# mainboard_V3_2.net
KiCad netlist of a schematic drawn in EasyEDA Pro
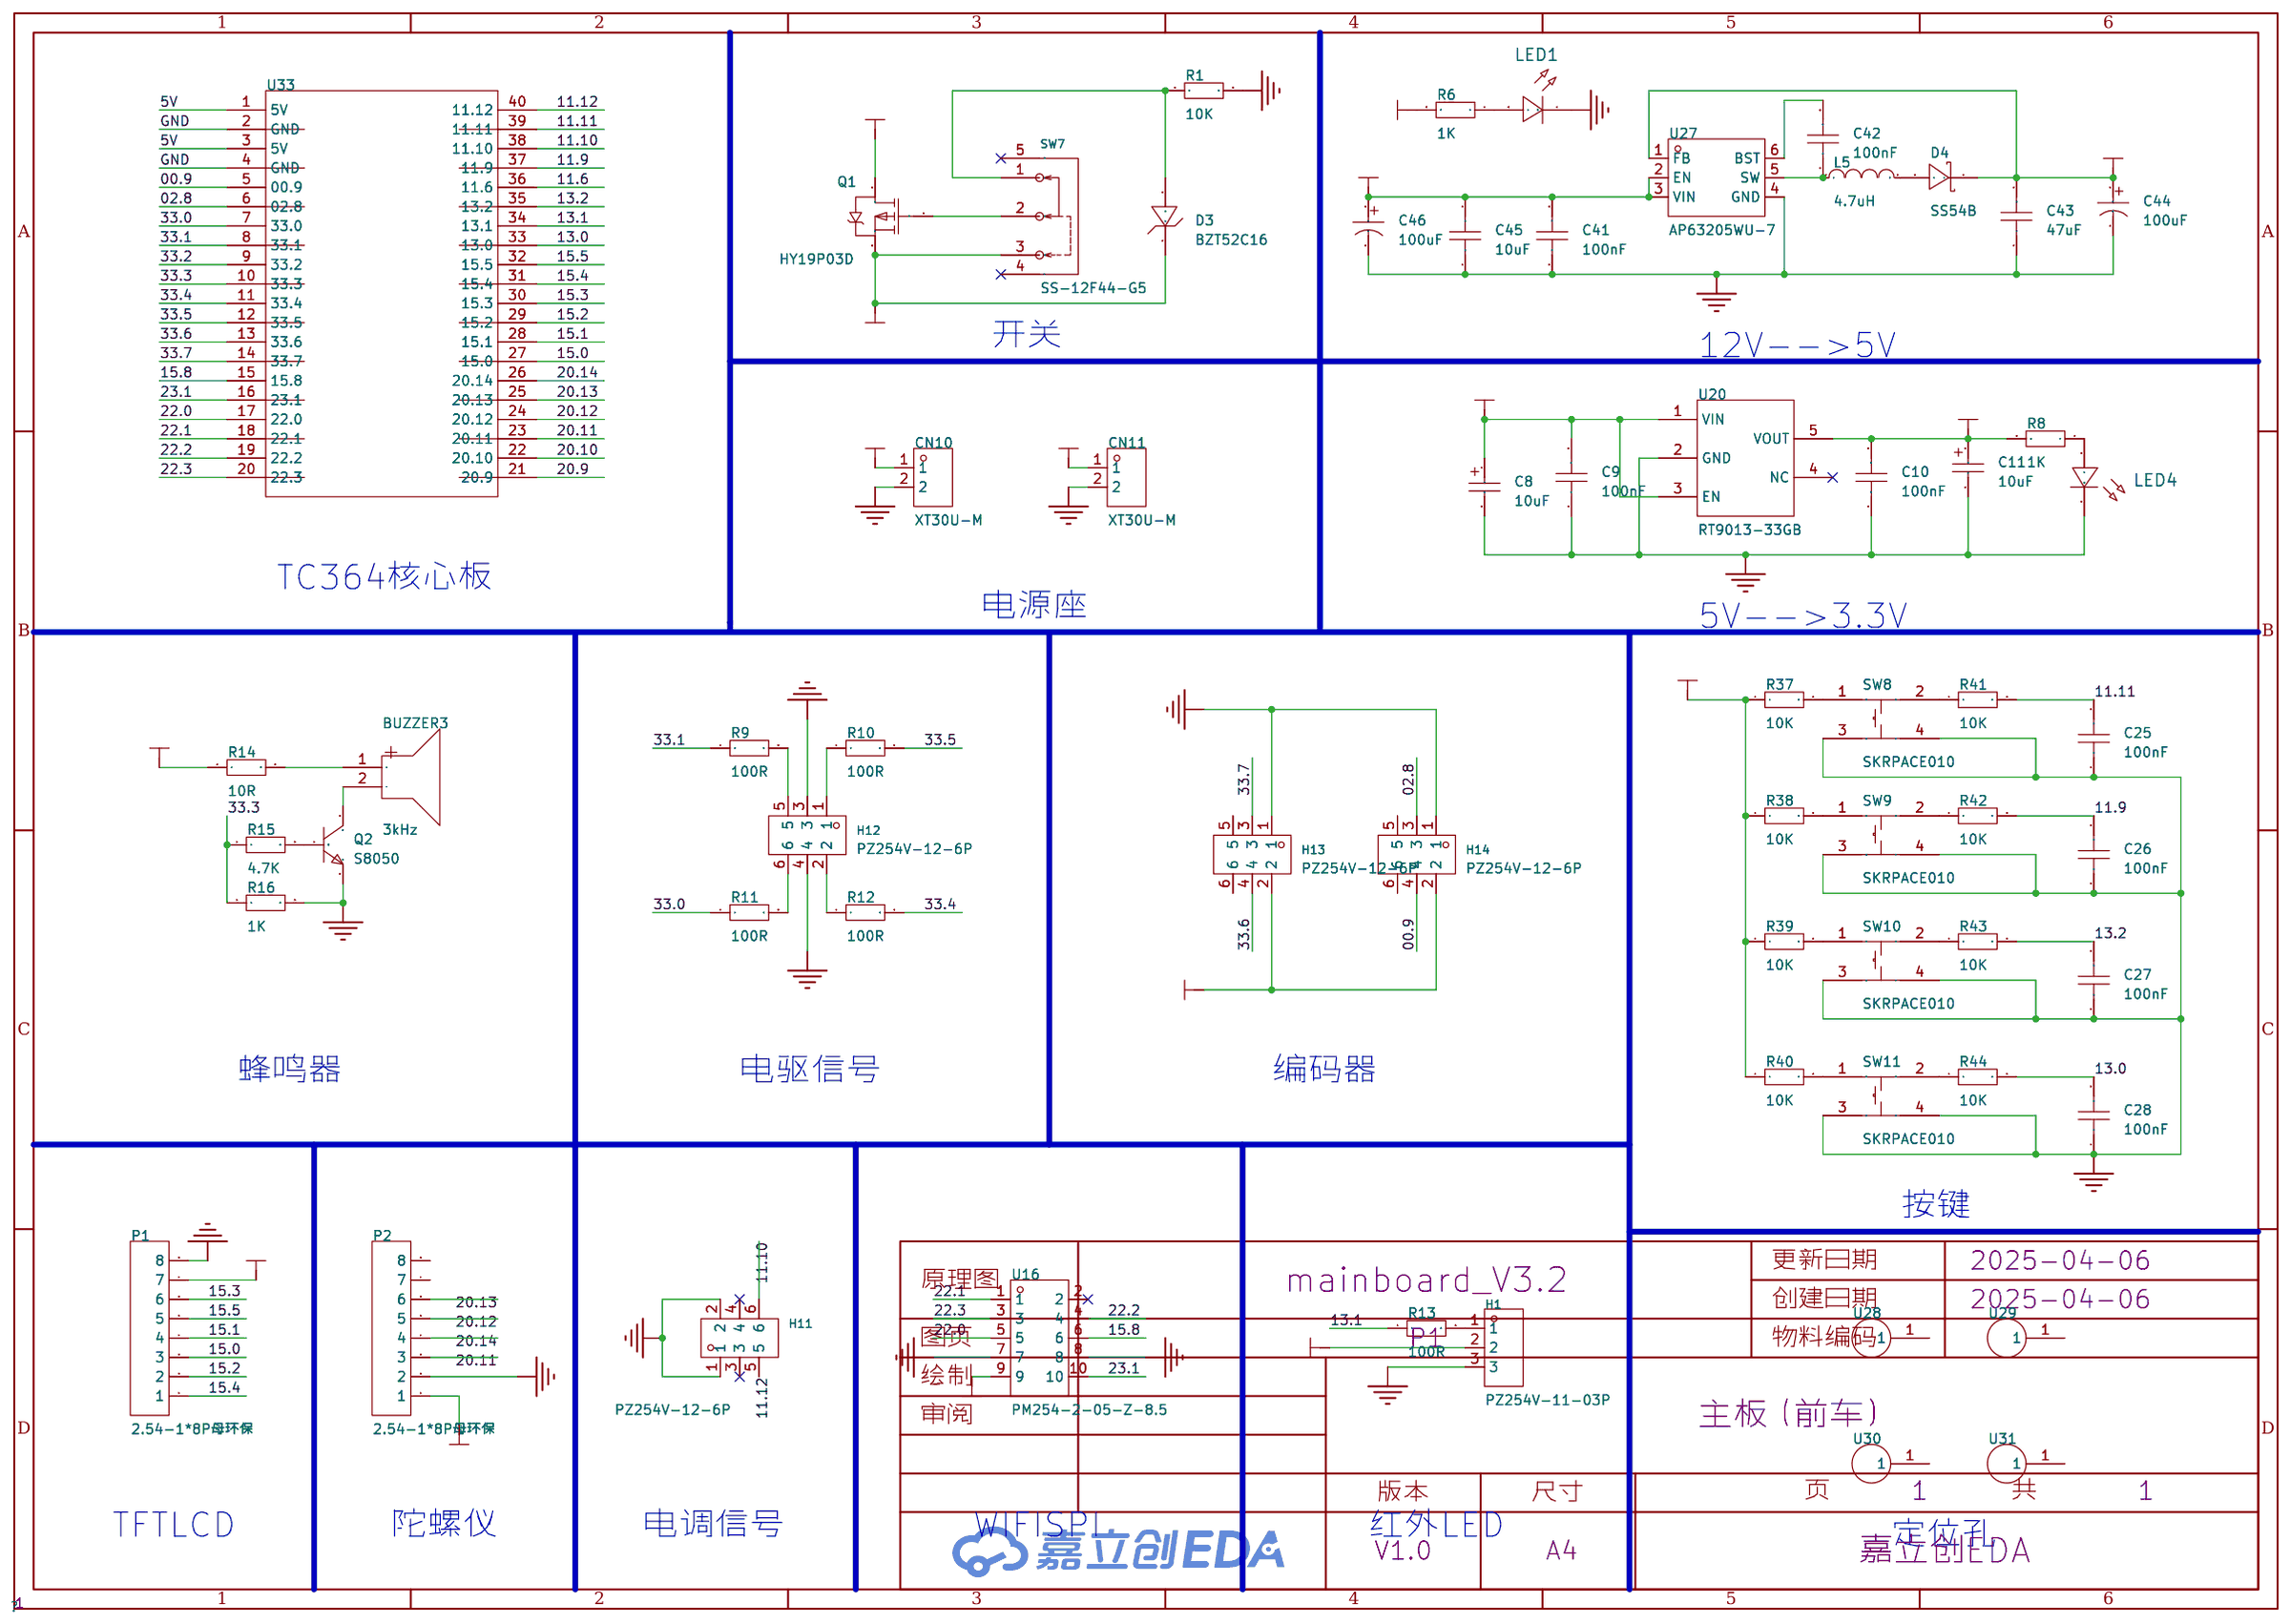
[diagram p0: schematic sheet]

(export (version "E")
  (design (tool "Eeschema 10.0.6"))
  (components
    (comp (ref "BUZZER3")
      (value "3kHz")
      (footprint "easyedapro:BUZ-TH_BD9.0-P5.00-D0.6-FD")
      (description "驱动方式:有源(内含驱动线路);构造类型:电磁式;频率:3kHz;声压(SPL):85dB@10cm;")
      (fields (field (name "Manufacturer Part") "HNB09A03") (field (name "Manufacturer") "华能"))
      (libsource (lib "easyedapro") (part "HNB09A03"))
    )
    (comp (ref "C8")
      (value "10uF")
      (footprint "easyedapro:CAP-SMD_L3.2-W1.6-RD-C7171")
      (description "容值:10uF;精度:±10%;额定电压:16V;等效串联电阻:3Ω@100kHz;")
      (fields (field (name "Manufacturer Part") "TAJA106K016RNJ") (field (name "Manufacturer") "Kyocera AVX"))
      (libsource (lib "easyedapro") (part "TAJA106K016RNJ"))
    )
    (comp (ref "C9")
      (value "100nF")
      (footprint "easyedapro:C0603")
      (description "容值:100nF;精度:±10%;额定电压:50V;材质(温度系数):X7R;")
      (fields
        (field (name "Manufacturer Part") "CC0603KRX7R9BB104")
        (field (name "Manufacturer") "YAGEO(国巨)")
      )
      (libsource (lib "easyedapro") (part "CC0603KRX7R9BB104"))
    )
    (comp (ref "C10")
      (value "100nF")
      (footprint "easyedapro:C0603")
      (description "容值:100nF;精度:±10%;额定电压:50V;材质(温度系数):X7R;")
      (fields
        (field (name "Manufacturer Part") "CC0603KRX7R9BB104")
        (field (name "Manufacturer") "YAGEO(国巨)")
      )
      (libsource (lib "easyedapro") (part "CC0603KRX7R9BB104"))
    )
    (comp (ref "C11")
      (value "10uF")
      (footprint "easyedapro:CAP-SMD_L3.2-W1.6-RD-C7171")
      (description "容值:10uF;精度:±10%;额定电压:16V;等效串联电阻:3Ω@100kHz;")
      (fields (field (name "Manufacturer Part") "TAJA106K016RNJ") (field (name "Manufacturer") "Kyocera AVX"))
      (libsource (lib "easyedapro") (part "TAJA106K016RNJ"))
    )
    (comp (ref "C25")
      (value "100nF")
      (footprint "easyedapro:C0603")
      (libsource (lib "easyedapro") (part "CapAcitance"))
    )
    (comp (ref "C26")
      (value "100nF")
      (footprint "easyedapro:C0603")
      (libsource (lib "easyedapro") (part "CapAcitance"))
    )
    (comp (ref "C27")
      (value "100nF")
      (footprint "easyedapro:C0603")
      (libsource (lib "easyedapro") (part "CapAcitance"))
    )
    (comp (ref "C28")
      (value "100nF")
      (footprint "easyedapro:C0603")
      (libsource (lib "easyedapro") (part "CapAcitance"))
    )
    (comp (ref "C41")
      (value "100nF")
      (footprint "easyedapro:C0603")
      (libsource (lib "easyedapro") (part "CapAcitance"))
    )
    (comp (ref "C42")
      (value "100nF")
      (footprint "easyedapro:C0603")
      (libsource (lib "easyedapro") (part "CapAcitance"))
    )
    (comp (ref "C43")
      (value "47uF")
      (footprint "easyedapro:C0805")
      (description "容值:47uF;精度:±20%;额定电压:10V;材质(温度系数):X5R;")
      (fields
        (field (name "Manufacturer Part") "CGA0805X5R476M100MT")
        (field (name "Manufacturer") "HRE(芯声)")
      )
      (libsource (lib "easyedapro") (part "CGA0805X5R476M100MT"))
    )
    (comp (ref "C44")
      (value "100uF")
      (footprint "easyedapro:CAP-TH_BD6.3-P2.50-D1.0-FD")
      (description "容值:100uF;精度:±20%;额定电压:35V;纹波电流:2.35A@100kHz;等效串联电阻:50mΩ@100kHz;类型:-;")
      (fields
        (field (name "Manufacturer Part") "SPZ1VM101E08O00RAXXX")
        (field (name "Manufacturer") "AISHI(艾华集团)")
      )
      (libsource (lib "easyedapro") (part "SPZ1VM101E08000R"))
    )
    (comp (ref "C45")
      (value "10uF")
      (footprint "easyedapro:C0603")
      (libsource (lib "easyedapro") (part "CapAcitance"))
    )
    (comp (ref "C46")
      (value "100uF")
      (footprint "easyedapro:CAP-TH_BD6.3-P2.50-D1.0-FD")
      (description "容值:100uF;精度:±20%;额定电压:35V;纹波电流:2.35A@100kHz;等效串联电阻:50mΩ@100kHz;类型:-;")
      (fields
        (field (name "Manufacturer Part") "SPZ1VM101E08O00RAXXX")
        (field (name "Manufacturer") "AISHI(艾华集团)")
      )
      (libsource (lib "easyedapro") (part "SPZ1VM101E08000R"))
    )
    (comp (ref "CN10")
      (value "XT30U-M")
      (footprint "easyedapro:CONN-TH_XT30U-M")
      (description "类别:-;类型1:-;")
      (fields (field (name "Manufacturer") "AMASS(艾迈斯)"))
      (libsource (lib "easyedapro") (part "XT30U-M"))
    )
    (comp (ref "CN11")
      (value "XT30U-M")
      (footprint "easyedapro:CONN-TH_XT30U-M")
      (description "类别:-;类型1:-;")
      (fields (field (name "Manufacturer") "AMASS(艾迈斯)"))
      (libsource (lib "easyedapro") (part "XT30U-M"))
    )
    (comp (ref "D3")
      (value "BZT52C16")
      (footprint "easyedapro:SOD-123_L2.7-W1.6-LS3.7-RD")
      (description "二极管配置:独立式;稳压值(标称值):16V;稳压值(范围):15.3V~17.1V;功率:500mW;精度:-;")
      (fields (field (name "Manufacturer") "BORN(伯恩半导体)"))
      (libsource (lib "easyedapro") (part "BZT52C16_C266570"))
    )
    (comp (ref "D4")
      (value "SS54B")
      (footprint "easyedapro:SMB_L4.6-W3.6-LS5.3-RD")
      (description "二极管配置:独立式;正向压降(Vf):550mV@5A;直流反向耐压(Vr):40V;整流电流:5A;")
      (fields (field (name "Manufacturer") "MDD(辰达半导体)"))
      (libsource (lib "easyedapro") (part "SS54"))
    )
    (comp (ref "H1")
      (value "PZ254V-11-03P")
      (footprint "easyedapro:HDR-TH_3P-P2.54-V-M")
      (fields (field (name "Manufacturer") "XFCN(兴飞)"))
      (libsource (lib "easyedapro") (part "PZ254V-11-03P_C2937625"))
    )
    (comp (ref "H11")
      (value "PZ254V-12-6P")
      (footprint "easyedapro:HDR-TH_6P-P2.54-V-M-R2-C3-S2.54")
      (fields (field (name "Manufacturer") "XFCN(兴飞)"))
      (libsource (lib "easyedapro") (part "PZ254V-12-6P"))
    )
    (comp (ref "H12")
      (value "PZ254V-12-6P")
      (footprint "easyedapro:HDR-TH_6P-P2.54-V-M-R2-C3-S2.54")
      (fields (field (name "Manufacturer") "XFCN(兴飞)"))
      (libsource (lib "easyedapro") (part "PZ254V-12-6P"))
    )
    (comp (ref "H13")
      (value "PZ254V-12-6P")
      (footprint "easyedapro:HDR-TH_6P-P2.54-V-M-R2-C3-S2.54")
      (fields (field (name "Manufacturer") "XFCN(兴飞)"))
      (libsource (lib "easyedapro") (part "PZ254V-12-6P"))
    )
    (comp (ref "H14")
      (value "PZ254V-12-6P")
      (footprint "easyedapro:HDR-TH_6P-P2.54-V-M-R2-C3-S2.54")
      (fields (field (name "Manufacturer") "XFCN(兴飞)"))
      (libsource (lib "easyedapro") (part "PZ254V-12-6P"))
    )
    (comp (ref "L5")
      (value "4.7uH")
      (footprint "easyedapro:IND-SMD_L7.0-W6.6")
      (description "电感值:4.7uH;精度:±20%;额定电流:6A;饱和电流(Isat):9A;类型:一体成型电感;")
      (fields (field (name "Manufacturer Part") "FXL0630-4R7-M") (field (name "Manufacturer") "cjiang(长江微电)"))
      (libsource (lib "easyedapro") (part "FXL0630-4R7-M"))
    )
    (comp (ref "LED1")
      (value "~")
      (footprint "easyedapro:LED_0603")
      (libsource (lib "easyedapro") (part "LED_R"))
    )
    (comp (ref "LED4")
      (value "~")
      (footprint "easyedapro:LED_0603")
      (libsource (lib "easyedapro") (part "LED_R"))
    )
    (comp (ref "P1")
      (value "2.54-1*8P母环保")
      (footprint "easyedapro:HDR-TH_8P-P2.54-V-F-1")
      (description "插孔结构:1x8P;间距:2.54mm;行距:-;安装类型:直插;排数:单排;总孔位数:8P;塑高:-;触头材质:-;触头镀层:-;")
      (fields (field (name "Manufacturer") "BOOMELE(博穆精密)"))
      (libsource (lib "easyedapro") (part "Header-Female-2.54_1x8"))
    )
    (comp (ref "P2")
      (value "2.54-1*8P母环保")
      (footprint "easyedapro:HDR-TH_8P-P2.54-V-F-1")
      (description "插孔结构:1x8P;间距:2.54mm;行距:-;安装类型:直插;排数:单排;总孔位数:8P;塑高:-;触头材质:-;触头镀层:-;")
      (fields (field (name "Manufacturer") "BOOMELE(博穆精密)"))
      (libsource (lib "easyedapro") (part "Header-Female-2.54_1x8"))
    )
    (comp (ref "Q1")
      (value "HY19P03D")
      (footprint "easyedapro:TO-252-2_L6.6-W6.1-P4.57-LS9.9-TL-CW")
      (fields (field (name "Manufacturer") "HUAYI(华羿微)"))
      (libsource (lib "easyedapro") (part "HY19P03D"))
    )
    (comp (ref "Q2")
      (value "S8050")
      (footprint "easyedapro:SOT-23-3_L2.9-W1.3-P1.90-LS2.4-BR")
      (description "晶体管类型:NPN;集电极电流(Ic):500mA;集射极击穿电压(Vceo):25V;功率(Pd):300mW;")
      (fields (field (name "Manufacturer") "YONGYUTAI(永裕泰)"))
      (libsource (lib "easyedapro") (part "S8050_C2891804"))
    )
    (comp (ref "R1") (value "10K") (footprint "easyedapro:R0603") (libsource (lib "easyedapro") (part "电阻")))
    (comp (ref "R6") (value "1K") (libsource (lib "easyedapro") (part "电阻")))
    (comp (ref "R8") (value "1K") (footprint "easyedapro:R0603") (libsource (lib "easyedapro") (part "电阻")))
    (comp (ref "R9") (value "100R") (footprint "easyedapro:R0603") (libsource (lib "easyedapro") (part "电阻")))
    (comp (ref "R10")
      (value "100R")
      (footprint "easyedapro:R0603")
      (libsource (lib "easyedapro") (part "电阻"))
    )
    (comp (ref "R11")
      (value "100R")
      (footprint "easyedapro:R0603")
      (libsource (lib "easyedapro") (part "电阻"))
    )
    (comp (ref "R12")
      (value "100R")
      (footprint "easyedapro:R0603")
      (libsource (lib "easyedapro") (part "电阻"))
    )
    (comp (ref "R13")
      (value "100R")
      (footprint "easyedapro:R0603")
      (libsource (lib "easyedapro") (part "电阻"))
    )
    (comp (ref "R14") (value "10R") (footprint "easyedapro:R0603") (libsource (lib "easyedapro") (part "电阻")))
    (comp (ref "R15")
      (value "4.7K")
      (footprint "easyedapro:R0603")
      (libsource (lib "easyedapro") (part "电阻"))
    )
    (comp (ref "R16") (value "1K") (footprint "easyedapro:R0603") (libsource (lib "easyedapro") (part "电阻")))
    (comp (ref "R37") (value "10K") (footprint "easyedapro:R0603") (libsource (lib "easyedapro") (part "电阻")))
    (comp (ref "R38") (value "10K") (footprint "easyedapro:R0603") (libsource (lib "easyedapro") (part "电阻")))
    (comp (ref "R39") (value "10K") (footprint "easyedapro:R0603") (libsource (lib "easyedapro") (part "电阻")))
    (comp (ref "R40") (value "10K") (footprint "easyedapro:R0603") (libsource (lib "easyedapro") (part "电阻")))
    (comp (ref "R41") (value "10K") (footprint "easyedapro:R0603") (libsource (lib "easyedapro") (part "电阻")))
    (comp (ref "R42") (value "10K") (footprint "easyedapro:R0603") (libsource (lib "easyedapro") (part "电阻")))
    (comp (ref "R43") (value "10K") (footprint "easyedapro:R0603") (libsource (lib "easyedapro") (part "电阻")))
    (comp (ref "R44") (value "10K") (footprint "easyedapro:R0603") (libsource (lib "easyedapro") (part "电阻")))
    (comp (ref "SW7")
      (value "SS-12F44-G5")
      (footprint "easyedapro:SW-TH_SS-12F44-G5")
      (description "额定电流(DC):-;额定电压(DC):-;额定电流(AC):-;额定电压(AC):-;电路结构:单刀双掷;安装方式:直插;机械寿命:5千次;")
      (fields (field (name "Manufacturer") "韩国韩荣"))
      (libsource (lib "easyedapro") (part "SS-12F44-G5"))
    )
    (comp (ref "SW8")
      (value "SKRPACE010")
      (footprint "easyedapro:KEY-SMD_4P-L4.2-W3.2-P2.20-LS4.6")
      (description "电路结构:单刀单掷;按钮形状:椭圆形按钮;安装方式:立贴;开关长度:4.2mm;开关宽度:3.2mm;开关高度:2.5mm;触点电流:50mA;额定电压(DC):16V;带灯:-;机械寿命:-;")
      (fields (field (name "Manufacturer") "ALPSALPINE(阿尔卑斯阿尔派)"))
      (libsource (lib "easyedapro") (part "SKRPACE010"))
    )
    (comp (ref "SW9")
      (value "SKRPACE010")
      (footprint "easyedapro:KEY-SMD_4P-L4.2-W3.2-P2.20-LS4.6")
      (description "电路结构:单刀单掷;按钮形状:椭圆形按钮;安装方式:立贴;开关长度:4.2mm;开关宽度:3.2mm;开关高度:2.5mm;触点电流:50mA;额定电压(DC):16V;带灯:-;机械寿命:-;")
      (fields (field (name "Manufacturer") "ALPSALPINE(阿尔卑斯阿尔派)"))
      (libsource (lib "easyedapro") (part "SKRPACE010"))
    )
    (comp (ref "SW10")
      (value "SKRPACE010")
      (footprint "easyedapro:KEY-SMD_4P-L4.2-W3.2-P2.20-LS4.6")
      (description "电路结构:单刀单掷;按钮形状:椭圆形按钮;安装方式:立贴;开关长度:4.2mm;开关宽度:3.2mm;开关高度:2.5mm;触点电流:50mA;额定电压(DC):16V;带灯:-;机械寿命:-;")
      (fields (field (name "Manufacturer") "ALPSALPINE(阿尔卑斯阿尔派)"))
      (libsource (lib "easyedapro") (part "SKRPACE010"))
    )
    (comp (ref "SW11")
      (value "SKRPACE010")
      (footprint "easyedapro:KEY-SMD_4P-L4.2-W3.2-P2.20-LS4.6")
      (description "电路结构:单刀单掷;按钮形状:椭圆形按钮;安装方式:立贴;开关长度:4.2mm;开关宽度:3.2mm;开关高度:2.5mm;触点电流:50mA;额定电压(DC):16V;带灯:-;机械寿命:-;")
      (fields (field (name "Manufacturer") "ALPSALPINE(阿尔卑斯阿尔派)"))
      (libsource (lib "easyedapro") (part "SKRPACE010"))
    )
    (comp (ref "U16")
      (value "PM254-2-05-Z-8.5")
      (footprint "easyedapro:HDR-TH_10P-P2.54-V-F-R2-C5-S2.54")
      (fields (field (name "Manufacturer") "HCTL(华灿天禄)"))
      (libsource (lib "easyedapro") (part "PM254-2-05-Z-8.5"))
    )
    (comp (ref "U20")
      (value "RT9013-33GB")
      (footprint "easyedapro:SOT-23-5_L3.0-W1.7-P0.95-LS2.8-BL")
      (description "输出类型:固定;输出极性:正;最大输入电压:5.5V;输出电压:3.3V;输出电流:500mA;电源纹波抑制比(PSRR):50dB@(10kHz);")
      (fields (field (name "Manufacturer") "RICHTEK(立锜)"))
      (libsource (lib "easyedapro") (part "RT9013-33GB"))
    )
    (comp (ref "U27")
      (value "AP63205WU-7")
      (footprint "easyedapro:TSOT-23-6_L2.9-W1.6-P0.95-LS2.8-BL")
      (description "功能类型:降压型;输出类型:固定;输入电压:3.8V~32V;输出电压:5V;输出电流:2A;")
      (fields (field (name "Manufacturer") "DIODES(美台)"))
      (libsource (lib "easyedapro") (part "AP63205WU-7"))
    )
    (comp (ref "U28")
      (value "~")
      (footprint "easyedapro:M3螺丝孔")
      (libsource (lib "easyedapro") (part "M3螺丝孔"))
    )
    (comp (ref "U29")
      (value "~")
      (footprint "easyedapro:M3螺丝孔")
      (libsource (lib "easyedapro") (part "M3螺丝孔"))
    )
    (comp (ref "U30")
      (value "~")
      (footprint "easyedapro:M3螺丝孔")
      (libsource (lib "easyedapro") (part "M3螺丝孔"))
    )
    (comp (ref "U31")
      (value "~")
      (footprint "easyedapro:M3螺丝孔")
      (libsource (lib "easyedapro") (part "M3螺丝孔"))
    )
    (comp (ref "U33")
      (value "~")
      (footprint "easyedapro:TC364_CoreBoard_V3.0")
      (libsource (lib "easyedapro") (part "TC364_CoreBoard_V3.0"))
    )
  )
  (nets
    (net (code "1") (name "/00.9") (class "Default")
      (node (ref "H14") (pin "4") (pinfunction "4_4") (pintype "unspecified"))
      (node (ref "U33") (pin "5") (pinfunction "00.9_5") (pintype "input"))
    )
    (net (code "2") (name "/02.8") (class "Default")
      (node (ref "H14") (pin "3") (pinfunction "3_3") (pintype "unspecified"))
      (node (ref "U33") (pin "6") (pinfunction "02.8_6") (pintype "input"))
    )
    (net (code "3") (name "/11.6") (class "Default")
      (node (ref "U33") (pin "36") (pinfunction "11.6_36") (pintype "input"))
    )
    (net (code "4") (name "/11.9") (class "Default")
      (node (ref "C26") (pin "2") (pinfunction "2_2") (pintype "input"))
      (node (ref "R42") (pin "2") (pinfunction "2_2") (pintype "input"))
      (node (ref "U33") (pin "37") (pinfunction "11.9_37") (pintype "input"))
    )
    (net (code "5") (name "/11.10") (class "Default")
      (node (ref "H11") (pin "6") (pinfunction "6_6") (pintype "unspecified"))
      (node (ref "U33") (pin "38") (pinfunction "11.10_38") (pintype "input"))
    )
    (net (code "6") (name "/11.11") (class "Default")
      (node (ref "C25") (pin "2") (pinfunction "2_2") (pintype "input"))
      (node (ref "R41") (pin "2") (pinfunction "2_2") (pintype "input"))
      (node (ref "U33") (pin "39") (pinfunction "11.11_39") (pintype "input"))
    )
    (net (code "7") (name "/11.12") (class "Default")
      (node (ref "H11") (pin "5") (pinfunction "5_5") (pintype "unspecified"))
      (node (ref "U33") (pin "40") (pinfunction "11.12_40") (pintype "input"))
    )
    (net (code "8") (name "/13.0") (class "Default")
      (node (ref "C28") (pin "2") (pinfunction "2_2") (pintype "input"))
      (node (ref "R44") (pin "2") (pinfunction "2_2") (pintype "input"))
      (node (ref "U33") (pin "33") (pinfunction "13.0_33") (pintype "input"))
    )
    (net (code "9") (name "/13.1") (class "Default")
      (node (ref "R13") (pin "1") (pinfunction "1_1") (pintype "input"))
      (node (ref "U33") (pin "34") (pinfunction "13.1_34") (pintype "input"))
    )
    (net (code "10") (name "/13.2") (class "Default")
      (node (ref "C27") (pin "2") (pinfunction "2_2") (pintype "input"))
      (node (ref "R43") (pin "2") (pinfunction "2_2") (pintype "input"))
      (node (ref "U33") (pin "35") (pinfunction "13.2_35") (pintype "input"))
    )
    (net (code "11") (name "/15.0") (class "Default")
      (node (ref "P1") (pin "3") (pinfunction "3_3") (pintype "input"))
      (node (ref "U33") (pin "27") (pinfunction "15.0_27") (pintype "input"))
    )
    (net (code "12") (name "/15.1") (class "Default")
      (node (ref "P1") (pin "4") (pinfunction "4_4") (pintype "input"))
      (node (ref "U33") (pin "28") (pinfunction "15.1_28") (pintype "input"))
    )
    (net (code "13") (name "/15.2") (class "Default")
      (node (ref "P1") (pin "2") (pinfunction "2_2") (pintype "input"))
      (node (ref "U33") (pin "29") (pinfunction "15.2_29") (pintype "input"))
    )
    (net (code "14") (name "/15.3") (class "Default")
      (node (ref "P1") (pin "6") (pinfunction "6_6") (pintype "input"))
      (node (ref "U33") (pin "30") (pinfunction "15.3_30") (pintype "input"))
    )
    (net (code "15") (name "/15.4") (class "Default")
      (node (ref "P1") (pin "1") (pinfunction "1_1") (pintype "input"))
      (node (ref "U33") (pin "31") (pinfunction "15.4_31") (pintype "input"))
    )
    (net (code "16") (name "/15.5") (class "Default")
      (node (ref "P1") (pin "5") (pinfunction "5_5") (pintype "input"))
      (node (ref "U33") (pin "32") (pinfunction "15.5_32") (pintype "input"))
    )
    (net (code "17") (name "/15.8") (class "Default")
      (node (ref "U16") (pin "6") (pinfunction "6_6") (pintype "unspecified"))
      (node (ref "U33") (pin "15") (pinfunction "15.8_15") (pintype "input"))
    )
    (net (code "18") (name "/20.9") (class "Default")
      (node (ref "U33") (pin "21") (pinfunction "20.9_21") (pintype "input"))
    )
    (net (code "19") (name "/20.10") (class "Default")
      (node (ref "U33") (pin "22") (pinfunction "20.10_22") (pintype "input"))
    )
    (net (code "20") (name "/20.11") (class "Default")
      (node (ref "P2") (pin "3") (pinfunction "3_3") (pintype "input"))
      (node (ref "U33") (pin "23") (pinfunction "20.11_23") (pintype "input"))
    )
    (net (code "21") (name "/20.12") (class "Default")
      (node (ref "P2") (pin "5") (pinfunction "5_5") (pintype "input"))
      (node (ref "U33") (pin "24") (pinfunction "20.12_24") (pintype "input"))
    )
    (net (code "22") (name "/20.13") (class "Default")
      (node (ref "P2") (pin "6") (pinfunction "6_6") (pintype "input"))
      (node (ref "U33") (pin "25") (pinfunction "20.13_25") (pintype "input"))
    )
    (net (code "23") (name "/20.14") (class "Default")
      (node (ref "P2") (pin "4") (pinfunction "4_4") (pintype "input"))
      (node (ref "U33") (pin "26") (pinfunction "20.14_26") (pintype "input"))
    )
    (net (code "24") (name "/22.0") (class "Default")
      (node (ref "U16") (pin "5") (pinfunction "5_5") (pintype "unspecified"))
      (node (ref "U33") (pin "17") (pinfunction "22.0_17") (pintype "input"))
    )
    (net (code "25") (name "/22.1") (class "Default")
      (node (ref "U16") (pin "1") (pinfunction "1_1") (pintype "unspecified"))
      (node (ref "U33") (pin "18") (pinfunction "22.1_18") (pintype "input"))
    )
    (net (code "26") (name "/22.2") (class "Default")
      (node (ref "U16") (pin "4") (pinfunction "4_4") (pintype "unspecified"))
      (node (ref "U33") (pin "19") (pinfunction "22.2_19") (pintype "input"))
    )
    (net (code "27") (name "/22.3") (class "Default")
      (node (ref "U16") (pin "3") (pinfunction "3_3") (pintype "unspecified"))
      (node (ref "U33") (pin "20") (pinfunction "22.3_20") (pintype "input"))
    )
    (net (code "28") (name "/23.1") (class "Default")
      (node (ref "U16") (pin "10") (pinfunction "10_10") (pintype "unspecified"))
      (node (ref "U33") (pin "16") (pinfunction "23.1_16") (pintype "input"))
    )
    (net (code "29") (name "/33.0") (class "Default")
      (node (ref "R11") (pin "1") (pinfunction "1_1") (pintype "input"))
      (node (ref "U33") (pin "7") (pinfunction "33.0_7") (pintype "input"))
    )
    (net (code "30") (name "/33.1") (class "Default")
      (node (ref "R9") (pin "1") (pinfunction "1_1") (pintype "input"))
      (node (ref "U33") (pin "8") (pinfunction "33.1_8") (pintype "input"))
    )
    (net (code "31") (name "/33.2") (class "Default")
      (node (ref "U33") (pin "9") (pinfunction "33.2_9") (pintype "input"))
    )
    (net (code "32") (name "/33.3") (class "Default")
      (node (ref "R15") (pin "1") (pinfunction "1_1") (pintype "input"))
      (node (ref "R16") (pin "1") (pinfunction "1_1") (pintype "input"))
      (node (ref "U33") (pin "10") (pinfunction "33.3_10") (pintype "input"))
    )
    (net (code "33") (name "/33.4") (class "Default")
      (node (ref "R12") (pin "2") (pinfunction "2_2") (pintype "input"))
      (node (ref "U33") (pin "11") (pinfunction "33.4_11") (pintype "input"))
    )
    (net (code "34") (name "/33.5") (class "Default")
      (node (ref "R10") (pin "2") (pinfunction "2_2") (pintype "input"))
      (node (ref "U33") (pin "12") (pinfunction "33.5_12") (pintype "input"))
    )
    (net (code "35") (name "/33.6") (class "Default")
      (node (ref "H13") (pin "4") (pinfunction "4_4") (pintype "unspecified"))
      (node (ref "U33") (pin "13") (pinfunction "33.6_13") (pintype "input"))
    )
    (net (code "36") (name "/33.7") (class "Default")
      (node (ref "H13") (pin "3") (pinfunction "3_3") (pintype "unspecified"))
      (node (ref "U33") (pin "14") (pinfunction "33.7_14") (pintype "input"))
    )
    (net (code "37") (name "3V3") (class "Default")
      (node (ref "C10") (pin "2") (pinfunction "2_2") (pintype "unspecified"))
      (node (ref "C11") (pin "1") (pinfunction "1_1") (pintype "input"))
      (node (ref "H13") (pin "2") (pinfunction "2_2") (pintype "unspecified"))
      (node (ref "H14") (pin "2") (pinfunction "2_2") (pintype "unspecified"))
      (node (ref "P1") (pin "7") (pinfunction "7_7") (pintype "input"))
      (node (ref "P2") (pin "1") (pinfunction "1_1") (pintype "input"))
      (node (ref "R14") (pin "1") (pinfunction "1_1") (pintype "input"))
      (node (ref "R37") (pin "1") (pinfunction "1_1") (pintype "input"))
      (node (ref "R38") (pin "1") (pinfunction "1_1") (pintype "input"))
      (node (ref "R39") (pin "1") (pinfunction "1_1") (pintype "input"))
      (node (ref "R40") (pin "1") (pinfunction "1_1") (pintype "input"))
      (node (ref "R8") (pin "2") (pinfunction "2_2") (pintype "input"))
      (node (ref "U20") (pin "5") (pinfunction "VOUT_5") (pintype "unspecified"))
    )
    (net (code "38") (name "5V") (class "Default")
      (node (ref "C43") (pin "2") (pinfunction "2_2") (pintype "unspecified"))
      (node (ref "C44") (pin "1") (pinfunction "1_1") (pintype "input"))
      (node (ref "C8") (pin "1") (pinfunction "1_1") (pintype "input"))
      (node (ref "C9") (pin "2") (pinfunction "2_2") (pintype "unspecified"))
      (node (ref "D4") (pin "1") (pinfunction "K_1") (pintype "unspecified"))
      (node (ref "H1") (pin "2") (pinfunction "2_2") (pintype "unspecified"))
      (node (ref "R6") (pin "2") (pinfunction "2_2") (pintype "input"))
      (node (ref "U16") (pin "9") (pinfunction "9_9") (pintype "unspecified"))
      (node (ref "U20") (pin "1") (pinfunction "VIN_1") (pintype "unspecified"))
      (node (ref "U20") (pin "3") (pinfunction "EN_3") (pintype "unspecified"))
      (node (ref "U27") (pin "1") (pinfunction "FB_1") (pintype "unspecified"))
      (node (ref "U33") (pin "1") (pinfunction "5V_1") (pintype "input"))
      (node (ref "U33") (pin "3") (pinfunction "5V_3") (pintype "input"))
    )
    (net (code "39") (name "GND") (class "Default")
      (node (ref "C10") (pin "1") (pinfunction "1_1") (pintype "unspecified"))
      (node (ref "C11") (pin "2") (pinfunction "2_2") (pintype "input"))
      (node (ref "C25") (pin "1") (pinfunction "1_1") (pintype "input"))
      (node (ref "C26") (pin "1") (pinfunction "1_1") (pintype "input"))
      (node (ref "C27") (pin "1") (pinfunction "1_1") (pintype "input"))
      (node (ref "C28") (pin "1") (pinfunction "1_1") (pintype "input"))
      (node (ref "C41") (pin "1") (pinfunction "1_1") (pintype "input"))
      (node (ref "C43") (pin "1") (pinfunction "1_1") (pintype "unspecified"))
      (node (ref "C44") (pin "2") (pinfunction "2_2") (pintype "input"))
      (node (ref "C45") (pin "1") (pinfunction "1_1") (pintype "input"))
      (node (ref "C46") (pin "2") (pinfunction "2_2") (pintype "input"))
      (node (ref "C8") (pin "2") (pinfunction "2_2") (pintype "input"))
      (node (ref "C9") (pin "1") (pinfunction "1_1") (pintype "unspecified"))
      (node (ref "CN10") (pin "2") (pinfunction "2_2") (pintype "unspecified"))
      (node (ref "CN11") (pin "2") (pinfunction "2_2") (pintype "unspecified"))
      (node (ref "H1") (pin "3") (pinfunction "3_3") (pintype "unspecified"))
      (node (ref "H11") (pin "1") (pinfunction "1_1") (pintype "unspecified"))
      (node (ref "H11") (pin "2") (pinfunction "2_2") (pintype "unspecified"))
      (node (ref "H12") (pin "3") (pinfunction "3_3") (pintype "unspecified"))
      (node (ref "H12") (pin "4") (pinfunction "4_4") (pintype "unspecified"))
      (node (ref "H13") (pin "1") (pinfunction "1_1") (pintype "unspecified"))
      (node (ref "H14") (pin "1") (pinfunction "1_1") (pintype "unspecified"))
      (node (ref "LED1") (pin "1") (pinfunction "C_1") (pintype "input"))
      (node (ref "LED4") (pin "1") (pinfunction "C_1") (pintype "input"))
      (node (ref "P1") (pin "8") (pinfunction "8_8") (pintype "input"))
      (node (ref "P2") (pin "2") (pinfunction "2_2") (pintype "input"))
      (node (ref "Q2") (pin "2") (pinfunction "E_2") (pintype "unspecified"))
      (node (ref "R1") (pin "2") (pinfunction "2_2") (pintype "input"))
      (node (ref "R16") (pin "2") (pinfunction "2_2") (pintype "input"))
      (node (ref "SW10") (pin "3") (pinfunction "3_3") (pintype "unspecified"))
      (node (ref "SW10") (pin "4") (pinfunction "4_4") (pintype "unspecified"))
      (node (ref "SW11") (pin "3") (pinfunction "3_3") (pintype "unspecified"))
      (node (ref "SW11") (pin "4") (pinfunction "4_4") (pintype "unspecified"))
      (node (ref "SW8") (pin "3") (pinfunction "3_3") (pintype "unspecified"))
      (node (ref "SW8") (pin "4") (pinfunction "4_4") (pintype "unspecified"))
      (node (ref "SW9") (pin "3") (pinfunction "3_3") (pintype "unspecified"))
      (node (ref "SW9") (pin "4") (pinfunction "4_4") (pintype "unspecified"))
      (node (ref "U16") (pin "7") (pinfunction "7_7") (pintype "unspecified"))
      (node (ref "U16") (pin "8") (pinfunction "8_8") (pintype "unspecified"))
      (node (ref "U20") (pin "2") (pinfunction "GND_2") (pintype "unspecified"))
      (node (ref "U27") (pin "4") (pinfunction "GND_4") (pintype "unspecified"))
      (node (ref "U33") (pin "2") (pinfunction "GND_2") (pintype "input"))
      (node (ref "U33") (pin "4") (pinfunction "GND_4") (pintype "input"))
    )
    (net (code "40") (name "Net-(BUZZER3-+)") (class "Default")
      (node (ref "BUZZER3") (pin "1") (pinfunction "+_1") (pintype "unspecified"))
      (node (ref "R14") (pin "2") (pinfunction "2_2") (pintype "input"))
    )
    (net (code "41") (name "Net-(BUZZER3--)") (class "Default")
      (node (ref "BUZZER3") (pin "2") (pinfunction "-_2") (pintype "unspecified"))
      (node (ref "Q2") (pin "3") (pinfunction "C_3") (pintype "unspecified"))
    )
    (net (code "42") (name "Net-(D3-Pad2)") (class "Default")
      (node (ref "D3") (pin "2") (pinfunction "2_2") (pintype "unspecified"))
      (node (ref "R1") (pin "1") (pinfunction "1_1") (pintype "input"))
      (node (ref "SW7") (pin "1") (pinfunction "1_1") (pintype "input"))
    )
    (net (code "43") (name "Net-(D4-A)") (class "Default")
      (node (ref "D4") (pin "2") (pinfunction "A_2") (pintype "unspecified"))
      (node (ref "L5") (pin "2") (pinfunction "2_2") (pintype "unspecified"))
    )
    (net (code "44") (name "Net-(H1-Pad1)") (class "Default")
      (node (ref "H1") (pin "1") (pinfunction "1_1") (pintype "unspecified"))
      (node (ref "R13") (pin "2") (pinfunction "2_2") (pintype "input"))
    )
    (net (code "45") (name "Net-(H12-Pad1)") (class "Default")
      (node (ref "H12") (pin "1") (pinfunction "1_1") (pintype "unspecified"))
      (node (ref "R10") (pin "1") (pinfunction "1_1") (pintype "input"))
    )
    (net (code "46") (name "Net-(H12-Pad2)") (class "Default")
      (node (ref "H12") (pin "2") (pinfunction "2_2") (pintype "unspecified"))
      (node (ref "R12") (pin "1") (pinfunction "1_1") (pintype "input"))
    )
    (net (code "47") (name "Net-(H12-Pad5)") (class "Default")
      (node (ref "H12") (pin "5") (pinfunction "5_5") (pintype "unspecified"))
      (node (ref "R9") (pin "2") (pinfunction "2_2") (pintype "input"))
    )
    (net (code "48") (name "Net-(H12-Pad6)") (class "Default")
      (node (ref "H12") (pin "6") (pinfunction "6_6") (pintype "unspecified"))
      (node (ref "R11") (pin "2") (pinfunction "2_2") (pintype "input"))
    )
    (net (code "49") (name "Net-(LED1-A)") (class "Default")
      (node (ref "LED1") (pin "2") (pinfunction "A_2") (pintype "input"))
      (node (ref "R6") (pin "1") (pinfunction "1_1") (pintype "input"))
    )
    (net (code "50") (name "Net-(LED4-A)") (class "Default")
      (node (ref "LED4") (pin "2") (pinfunction "A_2") (pintype "input"))
      (node (ref "R8") (pin "1") (pinfunction "1_1") (pintype "input"))
    )
    (net (code "51") (name "Net-(Q1-G)") (class "Default")
      (node (ref "Q1") (pin "1") (pinfunction "G_1") (pintype "input"))
      (node (ref "SW7") (pin "2") (pinfunction "2_2") (pintype "input"))
    )
    (net (code "52") (name "Net-(Q2-B)") (class "Default")
      (node (ref "Q2") (pin "1") (pinfunction "B_1") (pintype "unspecified"))
      (node (ref "R15") (pin "2") (pinfunction "2_2") (pintype "input"))
    )
    (net (code "53") (name "Net-(R37-Pad2)") (class "Default")
      (node (ref "R37") (pin "2") (pinfunction "2_2") (pintype "input"))
      (node (ref "SW8") (pin "1") (pinfunction "1_1") (pintype "unspecified"))
    )
    (net (code "54") (name "Net-(R38-Pad2)") (class "Default")
      (node (ref "R38") (pin "2") (pinfunction "2_2") (pintype "input"))
      (node (ref "SW9") (pin "1") (pinfunction "1_1") (pintype "unspecified"))
    )
    (net (code "55") (name "Net-(R39-Pad2)") (class "Default")
      (node (ref "R39") (pin "2") (pinfunction "2_2") (pintype "input"))
      (node (ref "SW10") (pin "1") (pinfunction "1_1") (pintype "unspecified"))
    )
    (net (code "56") (name "Net-(R40-Pad2)") (class "Default")
      (node (ref "R40") (pin "2") (pinfunction "2_2") (pintype "input"))
      (node (ref "SW11") (pin "1") (pinfunction "1_1") (pintype "unspecified"))
    )
    (net (code "57") (name "Net-(R41-Pad1)") (class "Default")
      (node (ref "R41") (pin "1") (pinfunction "1_1") (pintype "input"))
      (node (ref "SW8") (pin "2") (pinfunction "2_2") (pintype "unspecified"))
    )
    (net (code "58") (name "Net-(R42-Pad1)") (class "Default")
      (node (ref "R42") (pin "1") (pinfunction "1_1") (pintype "input"))
      (node (ref "SW9") (pin "2") (pinfunction "2_2") (pintype "unspecified"))
    )
    (net (code "59") (name "Net-(R43-Pad1)") (class "Default")
      (node (ref "R43") (pin "1") (pinfunction "1_1") (pintype "input"))
      (node (ref "SW10") (pin "2") (pinfunction "2_2") (pintype "unspecified"))
    )
    (net (code "60") (name "Net-(R44-Pad1)") (class "Default")
      (node (ref "R44") (pin "1") (pinfunction "1_1") (pintype "input"))
      (node (ref "SW11") (pin "2") (pinfunction "2_2") (pintype "unspecified"))
    )
    (net (code "61") (name "Net-(U27-BST)") (class "Default")
      (node (ref "C42") (pin "2") (pinfunction "2_2") (pintype "input"))
      (node (ref "U27") (pin "6") (pinfunction "BST_6") (pintype "unspecified"))
    )
    (net (code "62") (name "Net-(U27-SW)") (class "Default")
      (node (ref "C42") (pin "1") (pinfunction "1_1") (pintype "input"))
      (node (ref "L5") (pin "1") (pinfunction "1_1") (pintype "unspecified"))
      (node (ref "U27") (pin "5") (pinfunction "SW_5") (pintype "unspecified"))
    )
    (net (code "63") (name "VCCBAT") (class "Default")
      (node (ref "C41") (pin "2") (pinfunction "2_2") (pintype "input"))
      (node (ref "C45") (pin "2") (pinfunction "2_2") (pintype "input"))
      (node (ref "C46") (pin "1") (pinfunction "1_1") (pintype "input"))
      (node (ref "CN11") (pin "1") (pinfunction "1_1") (pintype "unspecified"))
      (node (ref "Q1") (pin "2") (pinfunction "D_2") (pintype "input"))
      (node (ref "U27") (pin "2") (pinfunction "EN_2") (pintype "unspecified"))
      (node (ref "U27") (pin "3") (pinfunction "VIN_3") (pintype "unspecified"))
    )
    (net (code "64") (name "VIN") (class "Default")
      (node (ref "CN10") (pin "1") (pinfunction "1_1") (pintype "unspecified"))
      (node (ref "D3") (pin "1") (pinfunction "1_1") (pintype "unspecified"))
      (node (ref "Q1") (pin "3") (pinfunction "S_3") (pintype "input"))
      (node (ref "SW7") (pin "3") (pinfunction "3_3") (pintype "input"))
    )
    (net (code "65") (name "unconnected-(H11-Pad3)") (class "Default")
      (node (ref "H11") (pin "3") (pinfunction "3_3") (pintype "unspecified+no_connect"))
    )
    (net (code "66") (name "unconnected-(H11-Pad4)") (class "Default")
      (node (ref "H11") (pin "4") (pinfunction "4_4") (pintype "unspecified+no_connect"))
    )
    (net (code "67") (name "unconnected-(H13-Pad5)") (class "Default")
      (node (ref "H13") (pin "5") (pinfunction "5_5") (pintype "unspecified"))
    )
    (net (code "68") (name "unconnected-(H13-Pad6)") (class "Default")
      (node (ref "H13") (pin "6") (pinfunction "6_6") (pintype "unspecified"))
    )
    (net (code "69") (name "unconnected-(H14-Pad5)") (class "Default")
      (node (ref "H14") (pin "5") (pinfunction "5_5") (pintype "unspecified"))
    )
    (net (code "70") (name "unconnected-(H14-Pad6)") (class "Default")
      (node (ref "H14") (pin "6") (pinfunction "6_6") (pintype "unspecified"))
    )
    (net (code "71") (name "unconnected-(P2-Pad7)") (class "Default")
      (node (ref "P2") (pin "7") (pinfunction "7_7") (pintype "input"))
    )
    (net (code "72") (name "unconnected-(P2-Pad8)") (class "Default")
      (node (ref "P2") (pin "8") (pinfunction "8_8") (pintype "input"))
    )
    (net (code "73") (name "unconnected-(SW7-Pad4)") (class "Default")
      (node (ref "SW7") (pin "4") (pinfunction "4_4") (pintype "input+no_connect"))
    )
    (net (code "74") (name "unconnected-(SW7-Pad5)") (class "Default")
      (node (ref "SW7") (pin "5") (pinfunction "5_5") (pintype "input+no_connect"))
    )
    (net (code "75") (name "unconnected-(U16-Pad2)") (class "Default")
      (node (ref "U16") (pin "2") (pinfunction "2_2") (pintype "unspecified+no_connect"))
    )
    (net (code "76") (name "unconnected-(U20-NC-Pad4)") (class "Default")
      (node (ref "U20") (pin "4") (pinfunction "NC_4") (pintype "unspecified+no_connect"))
    )
    (net (code "77") (name "unconnected-(U28-Pad1)") (class "Default")
      (node (ref "U28") (pin "1") (pinfunction "1_1") (pintype "input"))
    )
    (net (code "78") (name "unconnected-(U29-Pad1)") (class "Default")
      (node (ref "U29") (pin "1") (pinfunction "1_1") (pintype "input"))
    )
    (net (code "79") (name "unconnected-(U30-Pad1)") (class "Default")
      (node (ref "U30") (pin "1") (pinfunction "1_1") (pintype "input"))
    )
    (net (code "80") (name "unconnected-(U31-Pad1)") (class "Default")
      (node (ref "U31") (pin "1") (pinfunction "1_1") (pintype "input"))
    )
  )
)
